# STM32_V3LINKMOD.net
KiCad netlist of a schematic drawn in Altium Designer
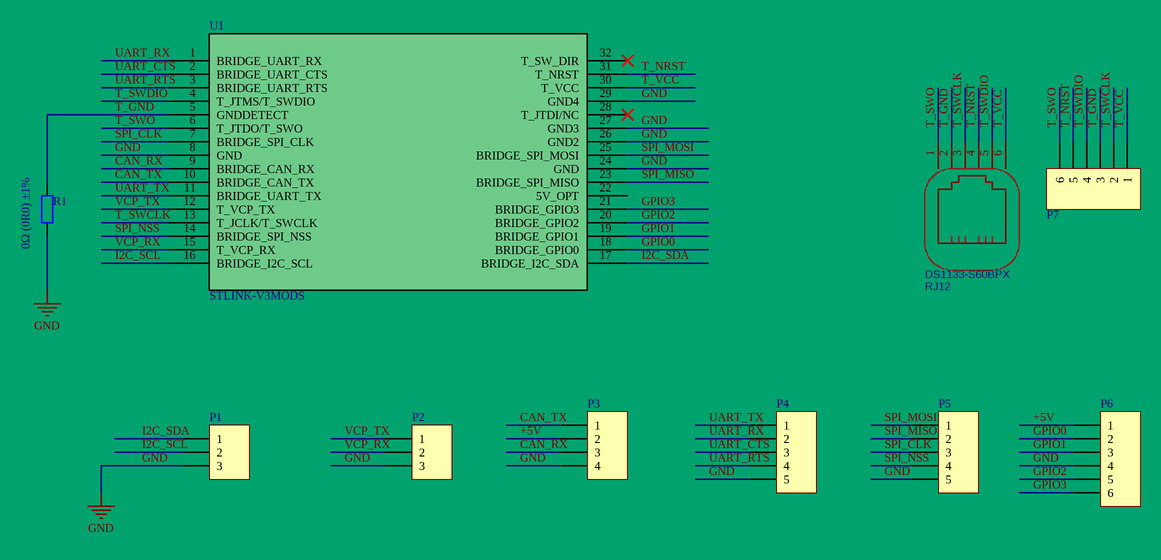
[diagram p0: STM32_V3LINKMOD.SchDoc]

(export (version "E")
  (design (tool "Eeschema 10.0.6"))
  (components
    (comp (ref "DS1133-S60BPX")
      (value "RJ12")
      (footprint "RJ11-TH_DS1133-S60BPX")
      (fields
        (field (name "BOM_MANUFACTURER PART") "DS1133-S60BPX")
        (field (name "BOM_SUPPLIER PART") "C77859")
      )
      (libsource (lib "Miscellaneous Devices LC") (part "RJ12-DS1133-S60BPX"))
    )
    (comp (ref "P1")
      (value "Header 3")
      (footprint "HDR1X3")
      (description "Header, 3-Pin")
      (fields (field (name "PUBLISHER") "Altium Limited"))
      (libsource (lib "Miscellaneous Connectors") (part "Header 3"))
    )
    (comp (ref "P2")
      (value "Header 3")
      (footprint "HDR1X3")
      (description "Header, 3-Pin")
      (fields (field (name "PUBLISHER") "Altium Limited"))
      (libsource (lib "Miscellaneous Connectors") (part "Header 3"))
    )
    (comp (ref "P3")
      (value "Header 4")
      (footprint "HDR1X4")
      (description "Header, 4-Pin")
      (fields (field (name "PUBLISHER") "Altium Limited"))
      (libsource (lib "Miscellaneous Connectors") (part "Header 4"))
    )
    (comp (ref "P4")
      (value "Header 5")
      (footprint "HDR1X5")
      (description "Header, 5-Pin")
      (fields (field (name "PUBLISHER") "Altium Limited"))
      (libsource (lib "Miscellaneous Connectors") (part "Header 5"))
    )
    (comp (ref "P5")
      (value "Header 5")
      (footprint "HDR1X5")
      (description "Header, 5-Pin")
      (fields (field (name "PUBLISHER") "Altium Limited"))
      (libsource (lib "Miscellaneous Connectors") (part "Header 5"))
    )
    (comp (ref "P6")
      (value "Header 6")
      (footprint "HDR1X6")
      (description "Header, 6-Pin")
      (fields (field (name "PUBLISHER") "Altium Limited"))
      (libsource (lib "Miscellaneous Connectors") (part "Header 6"))
    )
    (comp (ref "P7")
      (value "Header 6")
      (footprint "HDR1X6")
      (description "Header, 6-Pin")
      (fields (field (name "PUBLISHER") "Altium Limited"))
      (libsource (lib "") (part "Header 6_1"))
    )
    (comp (ref "R1")
      (value "0Ω (0R0) ±1%")
      (footprint "0805_R")
      (description "贴片电阻")
      (libsource (lib "Miscellaneous Devices LC") (part "0805 0Ω (0R0) 1%"))
    )
    (comp (ref "U1")
      (value "STLINK-V3MODS")
      (footprint "mod_stlink-v3m_m")
      (description "Imported")
      (fields
        (field (name "MANUFACTURER_PART_NUMBER") "STLINK-V3MOS")
        (field (name "COPYRIGHT") "Copyright (C) 2018 Accelerated Designs. All rights reserved")
      )
      (libsource (lib "Miscellaneous Devices LC") (part "STLINK-V3MODS"))
    )
  )
  (nets
    (net (code "1") (name "/+5V") (class "Default")
      (node (ref "P3") (pin "2") (pinfunction "2_2") (pintype "passive"))
      (node (ref "P6") (pin "1") (pinfunction "1_1") (pintype "passive"))
    )
    (net (code "2") (name "/CAN_RX") (class "Default")
      (node (ref "P3") (pin "3") (pinfunction "3_3") (pintype "passive"))
      (node (ref "U1") (pin "9") (pinfunction "BRIDGE_CAN_RX_9") (pintype "passive"))
    )
    (net (code "3") (name "/CAN_TX") (class "Default")
      (node (ref "P3") (pin "1") (pinfunction "1_1") (pintype "passive"))
      (node (ref "U1") (pin "10") (pinfunction "BRIDGE_CAN_TX_10") (pintype "passive"))
    )
    (net (code "4") (name "/GPIO0") (class "Default")
      (node (ref "P6") (pin "2") (pinfunction "2_2") (pintype "passive"))
      (node (ref "U1") (pin "18") (pinfunction "BRIDGE_GPIO0_18") (pintype "passive"))
    )
    (net (code "5") (name "/GPIO1") (class "Default")
      (node (ref "P6") (pin "3") (pinfunction "3_3") (pintype "passive"))
      (node (ref "U1") (pin "19") (pinfunction "BRIDGE_GPIO1_19") (pintype "passive"))
    )
    (net (code "6") (name "/GPIO2") (class "Default")
      (node (ref "P6") (pin "5") (pinfunction "5_5") (pintype "passive"))
      (node (ref "U1") (pin "20") (pinfunction "BRIDGE_GPIO2_20") (pintype "passive"))
    )
    (net (code "7") (name "/GPIO3") (class "Default")
      (node (ref "P6") (pin "6") (pinfunction "6_6") (pintype "passive"))
      (node (ref "U1") (pin "21") (pinfunction "BRIDGE_GPIO3_21") (pintype "passive"))
    )
    (net (code "8") (name "/I2C_SCL") (class "Default")
      (node (ref "P1") (pin "2") (pinfunction "2_2") (pintype "passive"))
      (node (ref "U1") (pin "16") (pinfunction "BRIDGE_I2C_SCL_16") (pintype "passive"))
    )
    (net (code "9") (name "/I2C_SDA") (class "Default")
      (node (ref "P1") (pin "1") (pinfunction "1_1") (pintype "passive"))
      (node (ref "U1") (pin "17") (pinfunction "BRIDGE_I2C_SDA_17") (pintype "passive"))
    )
    (net (code "10") (name "/SPI_CLK") (class "Default")
      (node (ref "P5") (pin "3") (pinfunction "3_3") (pintype "passive"))
      (node (ref "U1") (pin "7") (pinfunction "BRIDGE_SPI_CLK_7") (pintype "passive"))
    )
    (net (code "11") (name "/SPI_MISO") (class "Default")
      (node (ref "P5") (pin "2") (pinfunction "2_2") (pintype "passive"))
      (node (ref "U1") (pin "23") (pinfunction "BRIDGE_SPI_MISO_23") (pintype "passive"))
    )
    (net (code "12") (name "/SPI_MOSI") (class "Default")
      (node (ref "P5") (pin "1") (pinfunction "1_1") (pintype "passive"))
      (node (ref "U1") (pin "25") (pinfunction "BRIDGE_SPI_MOSI_25") (pintype "passive"))
    )
    (net (code "13") (name "/SPI_NSS") (class "Default")
      (node (ref "P5") (pin "4") (pinfunction "4_4") (pintype "passive"))
      (node (ref "U1") (pin "14") (pinfunction "BRIDGE_SPI_NSS_14") (pintype "passive"))
    )
    (net (code "14") (name "/T_GND") (class "Default")
      (node (ref "DS1133-S60BPX") (pin "2") (pinfunction "2_2") (pintype "passive"))
      (node (ref "P7") (pin "3") (pinfunction "3_3") (pintype "passive"))
      (node (ref "R1") (pin "2") (pinfunction "2_2") (pintype "passive"))
      (node (ref "U1") (pin "5") (pinfunction "GNDDETECT_5") (pintype "passive"))
    )
    (net (code "15") (name "/T_NRST") (class "Default")
      (node (ref "DS1133-S60BPX") (pin "4") (pinfunction "4_4") (pintype "passive"))
      (node (ref "P7") (pin "5") (pinfunction "5_5") (pintype "passive"))
      (node (ref "U1") (pin "31") (pinfunction "T_NRST_31") (pintype "passive"))
    )
    (net (code "16") (name "/T_SWCLK") (class "Default")
      (node (ref "DS1133-S60BPX") (pin "3") (pinfunction "3_3") (pintype "passive"))
      (node (ref "P7") (pin "2") (pinfunction "2_2") (pintype "passive"))
      (node (ref "U1") (pin "13") (pinfunction "T_JCLK/T_SWCLK_13") (pintype "passive"))
    )
    (net (code "17") (name "/T_SWDIO") (class "Default")
      (node (ref "DS1133-S60BPX") (pin "5") (pinfunction "5_5") (pintype "passive"))
      (node (ref "P7") (pin "4") (pinfunction "4_4") (pintype "passive"))
      (node (ref "U1") (pin "4") (pinfunction "T_JTMS/T_SWDIO_4") (pintype "passive"))
    )
    (net (code "18") (name "/T_SWO") (class "Default")
      (node (ref "DS1133-S60BPX") (pin "1") (pinfunction "1_1") (pintype "passive"))
      (node (ref "P7") (pin "6") (pinfunction "6_6") (pintype "passive"))
      (node (ref "U1") (pin "6") (pinfunction "T_JTDO/T_SWO_6") (pintype "passive"))
    )
    (net (code "19") (name "/T_VCC") (class "Default")
      (node (ref "DS1133-S60BPX") (pin "6") (pinfunction "6_6") (pintype "passive"))
      (node (ref "P7") (pin "1") (pinfunction "1_1") (pintype "passive"))
      (node (ref "U1") (pin "30") (pinfunction "T_VCC_30") (pintype "passive"))
    )
    (net (code "20") (name "/UART_CTS") (class "Default")
      (node (ref "P4") (pin "3") (pinfunction "3_3") (pintype "passive"))
      (node (ref "U1") (pin "2") (pinfunction "BRIDGE_UART_CTS_2") (pintype "passive"))
    )
    (net (code "21") (name "/UART_RTS") (class "Default")
      (node (ref "P4") (pin "4") (pinfunction "4_4") (pintype "passive"))
      (node (ref "U1") (pin "3") (pinfunction "BRIDGE_UART_RTS_3") (pintype "passive"))
    )
    (net (code "22") (name "/UART_RX") (class "Default")
      (node (ref "P4") (pin "2") (pinfunction "2_2") (pintype "passive"))
      (node (ref "U1") (pin "1") (pinfunction "BRIDGE_UART_RX_1") (pintype "passive"))
    )
    (net (code "23") (name "/UART_TX") (class "Default")
      (node (ref "P4") (pin "1") (pinfunction "1_1") (pintype "passive"))
      (node (ref "U1") (pin "11") (pinfunction "BRIDGE_UART_TX_11") (pintype "passive"))
    )
    (net (code "24") (name "/VCP_RX") (class "Default")
      (node (ref "P2") (pin "2") (pinfunction "2_2") (pintype "passive"))
      (node (ref "U1") (pin "15") (pinfunction "T_VCP_RX_15") (pintype "passive"))
    )
    (net (code "25") (name "/VCP_TX") (class "Default")
      (node (ref "P2") (pin "1") (pinfunction "1_1") (pintype "passive"))
      (node (ref "U1") (pin "12") (pinfunction "T_VCP_TX_12") (pintype "passive"))
    )
    (net (code "26") (name "GND") (class "Default")
      (node (ref "P1") (pin "3") (pinfunction "3_3") (pintype "passive"))
      (node (ref "P2") (pin "3") (pinfunction "3_3") (pintype "passive"))
      (node (ref "P3") (pin "4") (pinfunction "4_4") (pintype "passive"))
      (node (ref "P4") (pin "5") (pinfunction "5_5") (pintype "passive"))
      (node (ref "P5") (pin "5") (pinfunction "5_5") (pintype "passive"))
      (node (ref "P6") (pin "4") (pinfunction "4_4") (pintype "passive"))
      (node (ref "R1") (pin "1") (pinfunction "1_1") (pintype "passive"))
      (node (ref "U1") (pin "24") (pinfunction "GND_24") (pintype "passive"))
      (node (ref "U1") (pin "26") (pinfunction "GND2_26") (pintype "passive"))
      (node (ref "U1") (pin "27") (pinfunction "GND3_27") (pintype "passive"))
      (node (ref "U1") (pin "29") (pinfunction "GND4_29") (pintype "passive"))
      (node (ref "U1") (pin "8") (pinfunction "GND_8") (pintype "passive"))
    )
    (net (code "27") (name "unconnected-(U1-5V_OPT-Pad22)") (class "Default")
      (node (ref "U1") (pin "22") (pinfunction "5V_OPT_22") (pintype "passive"))
    )
    (net (code "28") (name "unconnected-(U1-T_JTDI{slash}NC-Pad28)") (class "Default")
      (node (ref "U1") (pin "28") (pinfunction "T_JTDI/NC_28") (pintype "passive+no_connect"))
    )
    (net (code "29") (name "unconnected-(U1-T_SW_DIR-Pad32)") (class "Default")
      (node (ref "U1") (pin "32") (pinfunction "T_SW_DIR_32") (pintype "passive+no_connect"))
    )
  )
)
